# isoSPI.net
KiCad netlist of a schematic drawn in Altium Designer
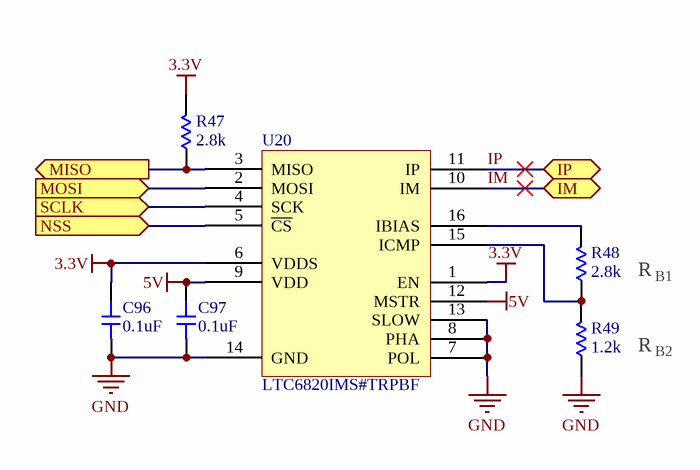
[diagram p0: isoSPI.SchDoc]

(export (version "E")
  (design (tool "Eeschema 10.0.6"))
  (components
    (comp (ref "C96")
      (value "0.1uF")
      (footprint "AMDC:0603-CAP")
      (description "Capacitor")
      (libsource (lib "AMDC") (part "Capacitor"))
    )
    (comp (ref "C97")
      (value "0.1uF")
      (footprint "AMDC:0603-CAP")
      (description "Capacitor")
      (libsource (lib "AMDC") (part "Capacitor"))
    )
    (comp (ref "R47")
      (value "2.8k")
      (footprint "AMDC:0603-RES")
      (description "Resistor")
      (libsource (lib "AMDC") (part "Resistor"))
    )
    (comp (ref "R48")
      (value "2.8k")
      (footprint "AMDC:0603-RES")
      (description "Resistor")
      (libsource (lib "AMDC") (part "Resistor"))
    )
    (comp (ref "R49")
      (value "1.2k")
      (footprint "AMDC:0603-RES")
      (description "Resistor")
      (libsource (lib "AMDC") (part "Resistor"))
    )
    (comp (ref "U20")
      (value "LTC6820IMS#TRPBF")
      (footprint "AMDC:TSSOP50P490X110-16N")
      (description "IC INTERFACE SPECIALIZED 16MSOP")
      (libsource (lib "AMDC") (part "LTC6820IMS#TRPBF"))
    )
  )
  (nets
    (net (code "1") (name "/IM") (class "Default")
      (node (ref "U20") (pin "10") (pinfunction "IM_10") (pintype "passive"))
    )
    (net (code "2") (name "/IP") (class "Default")
      (node (ref "U20") (pin "11") (pinfunction "IP_11") (pintype "passive"))
    )
    (net (code "3") (name "/MISO") (class "Default")
      (node (ref "R47") (pin "1") (pinfunction "1_1") (pintype "passive"))
      (node (ref "U20") (pin "3") (pinfunction "MISO_3") (pintype "passive"))
    )
    (net (code "4") (name "/MOSI") (class "Default")
      (node (ref "U20") (pin "2") (pinfunction "MOSI_2") (pintype "passive"))
    )
    (net (code "5") (name "/NSS") (class "Default")
      (node (ref "U20") (pin "5") (pinfunction "~{CS}_5") (pintype "passive"))
    )
    (net (code "6") (name "/SCLK") (class "Default")
      (node (ref "U20") (pin "4") (pinfunction "SCK_4") (pintype "passive"))
    )
    (net (code "7") (name "3.3V") (class "Default")
      (node (ref "C96") (pin "2") (pinfunction "2_2") (pintype "passive"))
      (node (ref "R47") (pin "2") (pinfunction "2_2") (pintype "passive"))
      (node (ref "U20") (pin "1") (pinfunction "EN_1") (pintype "passive"))
      (node (ref "U20") (pin "6") (pinfunction "VDDS_6") (pintype "passive"))
    )
    (net (code "8") (name "5V") (class "Default")
      (node (ref "C97") (pin "2") (pinfunction "2_2") (pintype "passive"))
      (node (ref "U20") (pin "12") (pinfunction "MSTR_12") (pintype "passive"))
      (node (ref "U20") (pin "9") (pinfunction "VDD_9") (pintype "passive"))
    )
    (net (code "9") (name "GND") (class "Default")
      (node (ref "C96") (pin "1") (pinfunction "1_1") (pintype "passive"))
      (node (ref "C97") (pin "1") (pinfunction "1_1") (pintype "passive"))
      (node (ref "R49") (pin "1") (pinfunction "1_1") (pintype "passive"))
      (node (ref "U20") (pin "13") (pinfunction "SLOW_13") (pintype "passive"))
      (node (ref "U20") (pin "14") (pinfunction "GND_14") (pintype "passive"))
      (node (ref "U20") (pin "7") (pinfunction "POL_7") (pintype "passive"))
      (node (ref "U20") (pin "8") (pinfunction "PHA_8") (pintype "passive"))
    )
    (net (code "10") (name "Net-(U20-IBIAS)") (class "Default")
      (node (ref "R48") (pin "2") (pinfunction "2_2") (pintype "passive"))
      (node (ref "U20") (pin "16") (pinfunction "IBIAS_16") (pintype "passive"))
    )
    (net (code "11") (name "Net-(U20-ICMP)") (class "Default")
      (node (ref "R48") (pin "1") (pinfunction "1_1") (pintype "passive"))
      (node (ref "R49") (pin "2") (pinfunction "2_2") (pintype "passive"))
      (node (ref "U20") (pin "15") (pinfunction "ICMP_15") (pintype "passive"))
    )
  )
)
